# Fuel_Sensor.net
KiCad netlist of a schematic drawn in EAGLE
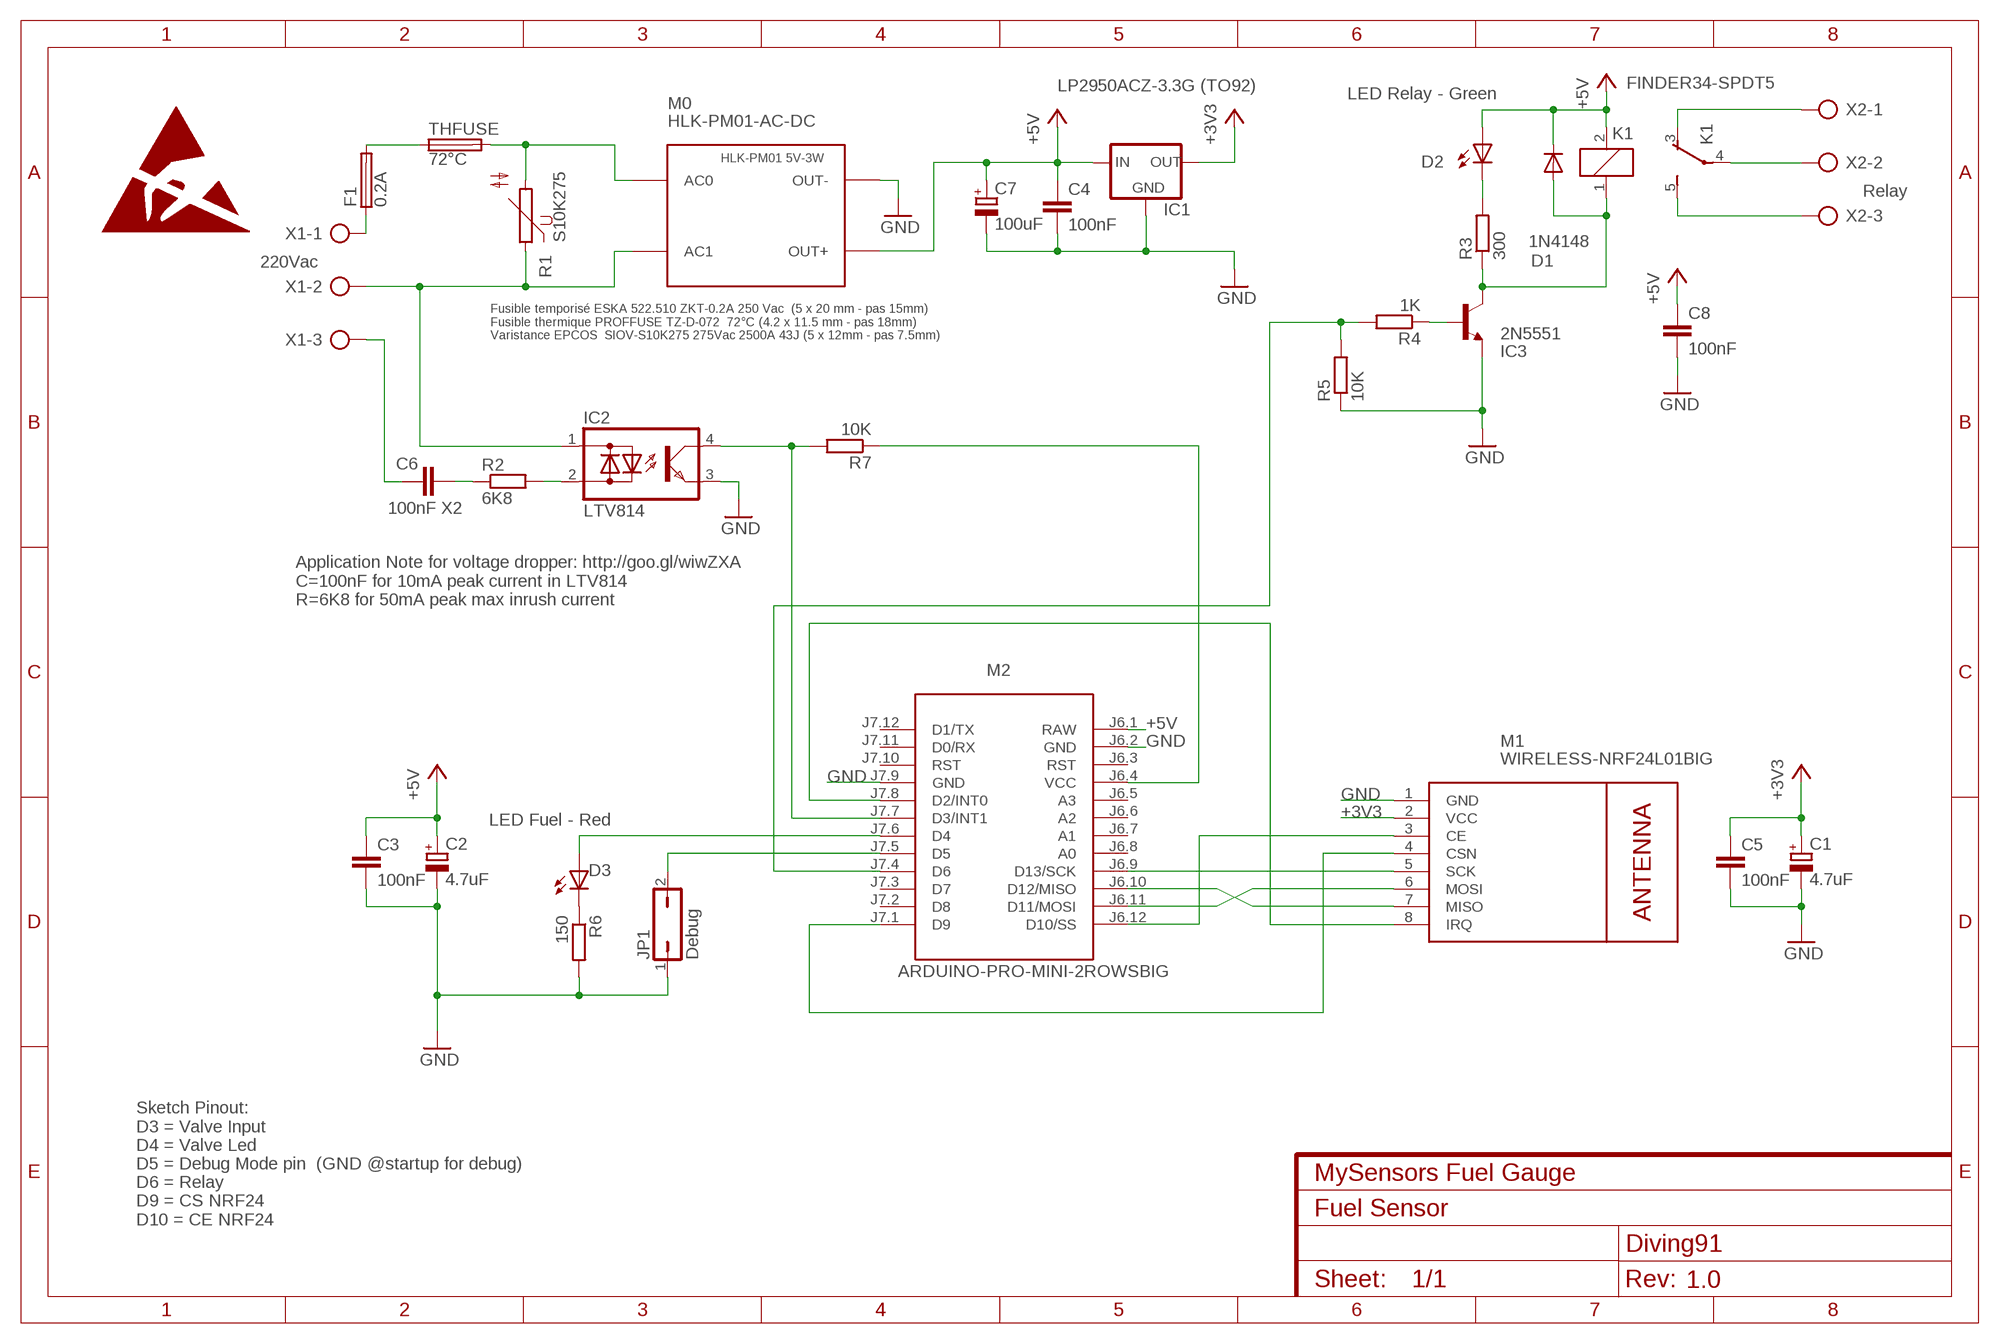
[diagram p0: schematic, sheet 1]

(export (version "E")
  (design (tool "Eeschema 10.0.6"))
  (components
    (comp (ref "C1")
      (value "4.7uF")
      (footprint "eagle-import:E2-5")
      (libsource (lib "eagle-import") (part "CPOL-RADE2-5"))
    )
    (comp (ref "C2")
      (value "4.7uF")
      (footprint "eagle-import:E2-5")
      (libsource (lib "eagle-import") (part "CPOL-RADE2-5"))
    )
    (comp (ref "C3")
      (value "100nF")
      (footprint "eagle-import:C-C320")
      (libsource (lib "eagle-import") (part "CNP-RADC320"))
    )
    (comp (ref "C4")
      (value "100nF")
      (footprint "eagle-import:C-C320")
      (libsource (lib "eagle-import") (part "CNP-RADC320"))
    )
    (comp (ref "C5")
      (value "100nF")
      (footprint "eagle-import:C-C320")
      (libsource (lib "eagle-import") (part "CNP-RADC320"))
    )
    (comp (ref "C6")
      (value "100nF X2")
      (footprint "eagle-import:C-B32922-MKPX2")
      (libsource (lib "eagle-import") (part "CNP-RADB32922"))
    )
    (comp (ref "C7")
      (value "100uF")
      (footprint "eagle-import:E3-8")
      (libsource (lib "eagle-import") (part "CPOL-RADE3-8"))
    )
    (comp (ref "C8")
      (value "100nF")
      (footprint "eagle-import:C-C320")
      (libsource (lib "eagle-import") (part "CNP-RADC320"))
    )
    (comp (ref "D1")
      (value "1N4148")
      (footprint "eagle-import:DO35")
      (libsource (lib "eagle-import") (part "1N4148DO35"))
    )
    (comp (ref "D2")
      (value "LED Relay - Green")
      (footprint "eagle-import:LED5MM")
      (libsource (lib "eagle-import") (part "LED5MM"))
    )
    (comp (ref "D3")
      (value "LED Fuel - Red")
      (footprint "eagle-import:LED5MM")
      (libsource (lib "eagle-import") (part "LED5MM"))
    )
    (comp (ref "F1")
      (value "0.2A")
      (footprint "eagle-import:PTF75")
      (libsource (lib "eagle-import") (part "PTF75"))
    )
    (comp (ref "IC1")
      (value "LP2950ACZ-3.3G (TO92)")
      (footprint "eagle-import:DC-DC-TO92L")
      (libsource (lib "eagle-import") (part "78LXXTO92L"))
    )
    (comp (ref "IC2")
      (value "LTV814")
      (footprint "eagle-import:DIL04")
      (libsource (lib "eagle-import") (part "LTV814"))
    )
    (comp (ref "IC3")
      (value "2N5551")
      (footprint "eagle-import:T-T092L")
      (libsource (lib "eagle-import") (part "T-NPNT092L"))
    )
    (comp (ref "JP1")
      (value "Debug")
      (footprint "eagle-import:JUMPER2")
      (libsource (lib "eagle-import") (part "JUMPER2"))
    )
    (comp (ref "K1")
      (value "FINDER34-SPDT5")
      (footprint "eagle-import:FINDER34-SPDT")
      (libsource (lib "eagle-import") (part "FINDER34-SPDT5"))
    )
    (comp (ref "M0")
      (value "HLK-PM01-AC-DC")
      (footprint "eagle-import:HLK-PM01-AC-DC")
      (libsource (lib "eagle-import") (part "HLK-PM01-AC-DC"))
    )
    (comp (ref "M1")
      (value "WIRELESS-NRF24L01BIG")
      (footprint "eagle-import:WIRELESS-NRF24L01-DIY")
      (libsource (lib "eagle-import") (part "WIRELESS-NRF24L01BIG"))
    )
    (comp (ref "M2")
      (value "ARDUINO-PRO-MINI-2ROWSBIG")
      (footprint "eagle-import:ARDUINO-PRO-MINI-2ROWS-DIY")
      (libsource (lib "eagle-import") (part "ARDUINO-PRO-MINI-2ROWSBIG"))
    )
    (comp (ref "R1")
      (value "S10K275")
      (footprint "eagle-import:S10K275")
      (libsource (lib "eagle-import") (part "S10K275"))
    )
    (comp (ref "R2")
      (value "6K8")
      (footprint "eagle-import:PMR02S")
      (libsource (lib "eagle-import") (part "RPMR02S"))
    )
    (comp (ref "R3")
      (value "300")
      (footprint "eagle-import:PMR0.25W")
      (libsource (lib "eagle-import") (part "RPMR0.25W"))
    )
    (comp (ref "R4")
      (value "1K")
      (footprint "eagle-import:PMR0.25W")
      (libsource (lib "eagle-import") (part "RPMR0.25W"))
    )
    (comp (ref "R5")
      (value "10K")
      (footprint "eagle-import:PMR0.25W")
      (libsource (lib "eagle-import") (part "RPMR0.25W"))
    )
    (comp (ref "R6")
      (value "150")
      (footprint "eagle-import:PMR0.25W")
      (libsource (lib "eagle-import") (part "RPMR0.25W"))
    )
    (comp (ref "R7")
      (value "10K")
      (footprint "eagle-import:PMR0.25W")
      (libsource (lib "eagle-import") (part "RPMR0.25W"))
    )
    (comp (ref "THFUSE")
      (value "72°C")
      (footprint "eagle-import:PROFFUSE-TZ-D")
      (libsource (lib "eagle-import") (part "PROFFUSE-TZ-D"))
    )
    (comp (ref "X1")
      (value "220Vac")
      (footprint "eagle-import:DG301-5.0-3")
      (libsource (lib "eagle-import") (part "DG301-5.0-3"))
    )
    (comp (ref "X2")
      (value "Relay")
      (footprint "eagle-import:DG301-5.0-3")
      (libsource (lib "eagle-import") (part "DG301-5.0-3"))
    )
  )
  (nets
    (net (code "1") (name "+3V3") (class "Default")
      (node (ref "C1") (pin "+") (pinfunction "+_+") (pintype "passive"))
      (node (ref "C5") (pin "1") (pinfunction "1_1") (pintype "passive"))
      (node (ref "IC1") (pin "OUT") (pinfunction "OUT_OUT") (pintype "passive"))
      (node (ref "M1") (pin "2") (pinfunction "VCC_2") (pintype "power_in"))
    )
    (net (code "2") (name "+5V") (class "Default")
      (node (ref "C2") (pin "+") (pinfunction "+_+") (pintype "passive"))
      (node (ref "C3") (pin "1") (pinfunction "1_1") (pintype "passive"))
      (node (ref "C4") (pin "1") (pinfunction "1_1") (pintype "passive"))
      (node (ref "C7") (pin "+") (pinfunction "+_+") (pintype "passive"))
      (node (ref "C8") (pin "1") (pinfunction "1_1") (pintype "passive"))
      (node (ref "D1") (pin "C") (pinfunction "C_C") (pintype "passive"))
      (node (ref "D2") (pin "A") (pinfunction "A_A") (pintype "passive"))
      (node (ref "IC1") (pin "IN") (pinfunction "IN_IN") (pintype "input"))
      (node (ref "K1") (pin "2") (pinfunction "2_2") (pintype "passive"))
      (node (ref "M0") (pin "OUT+") (pinfunction "OUT+_OUT+") (pintype "bidirectional"))
      (node (ref "M2") (pin "J6.1") (pinfunction "RAW_J6.1") (pintype "power_in"))
    )
    (net (code "3") (name "GND") (class "Default")
      (node (ref "C1") (pin "-") (pinfunction "-_-") (pintype "passive"))
      (node (ref "C2") (pin "-") (pinfunction "-_-") (pintype "passive"))
      (node (ref "C3") (pin "2") (pinfunction "2_2") (pintype "passive"))
      (node (ref "C4") (pin "2") (pinfunction "2_2") (pintype "passive"))
      (node (ref "C5") (pin "2") (pinfunction "2_2") (pintype "passive"))
      (node (ref "C7") (pin "-") (pinfunction "-_-") (pintype "passive"))
      (node (ref "C8") (pin "2") (pinfunction "2_2") (pintype "passive"))
      (node (ref "IC1") (pin "GND") (pinfunction "GND_GND") (pintype "input"))
      (node (ref "IC2") (pin "3") (pinfunction "E_3") (pintype "passive"))
      (node (ref "IC3") (pin "E") (pinfunction "E_E") (pintype "passive"))
      (node (ref "JP1") (pin "1") (pinfunction "1_1") (pintype "passive"))
      (node (ref "M0") (pin "OUT-") (pinfunction "OUT-_OUT-") (pintype "bidirectional"))
      (node (ref "M1") (pin "1") (pinfunction "GND_1") (pintype "power_in"))
      (node (ref "M2") (pin "J6.2") (pinfunction "GND_J6.2") (pintype "power_in"))
      (node (ref "M2") (pin "J7.9") (pinfunction "GND_J7.9") (pintype "power_in"))
      (node (ref "R5") (pin "1") (pinfunction "1_1") (pintype "passive"))
      (node (ref "R6") (pin "2") (pinfunction "2_2") (pintype "passive"))
    )
    (net (code "4") (name "Net-(C6-Pad2)") (class "Default")
      (node (ref "C6") (pin "2") (pinfunction "2_2") (pintype "passive"))
      (node (ref "R2") (pin "1") (pinfunction "1_1") (pintype "passive"))
    )
    (net (code "5") (name "Net-(D1-PadA)") (class "Default")
      (node (ref "D1") (pin "A") (pinfunction "A_A") (pintype "passive"))
      (node (ref "IC3") (pin "C") (pinfunction "C_C") (pintype "passive"))
      (node (ref "K1") (pin "1") (pinfunction "1_1") (pintype "passive"))
      (node (ref "R3") (pin "1") (pinfunction "1_1") (pintype "passive"))
    )
    (net (code "6") (name "Net-(D2-C)") (class "Default")
      (node (ref "D2") (pin "K") (pinfunction "C_K") (pintype "passive"))
      (node (ref "R3") (pin "2") (pinfunction "2_2") (pintype "passive"))
    )
    (net (code "7") (name "Net-(D3-C)") (class "Default")
      (node (ref "D3") (pin "K") (pinfunction "C_K") (pintype "passive"))
      (node (ref "R6") (pin "1") (pinfunction "1_1") (pintype "passive"))
    )
    (net (code "8") (name "Net-(F1-Pad2)") (class "Default")
      (node (ref "F1") (pin "2") (pinfunction "2_2") (pintype "passive"))
      (node (ref "THFUSE") (pin "1") (pinfunction "1_1") (pintype "passive"))
    )
    (net (code "9") (name "Net-(IC2-AC1)") (class "Default")
      (node (ref "IC2") (pin "1") (pinfunction "AC1_1") (pintype "passive"))
      (node (ref "M0") (pin "AC1") (pinfunction "AC1_AC1") (pintype "bidirectional"))
      (node (ref "R1") (pin "1") (pinfunction "1_1") (pintype "passive"))
      (node (ref "X1") (pin "2") (pinfunction "KL_2") (pintype "passive"))
    )
    (net (code "10") (name "Net-(IC2-AC2)") (class "Default")
      (node (ref "IC2") (pin "2") (pinfunction "AC2_2") (pintype "passive"))
      (node (ref "R2") (pin "2") (pinfunction "2_2") (pintype "passive"))
    )
    (net (code "11") (name "Net-(IC2-C)") (class "Default")
      (node (ref "IC2") (pin "4") (pinfunction "C_4") (pintype "passive"))
      (node (ref "M2") (pin "J7.7") (pinfunction "D3/INT1_J7.7") (pintype "bidirectional"))
      (node (ref "R7") (pin "2") (pinfunction "2_2") (pintype "passive"))
    )
    (net (code "12") (name "Net-(IC3-PadB)") (class "Default")
      (node (ref "IC3") (pin "B") (pinfunction "B_B") (pintype "passive"))
      (node (ref "R4") (pin "1") (pinfunction "1_1") (pintype "passive"))
    )
    (net (code "13") (name "Net-(K1A-O)") (class "Default")
      (node (ref "K1") (pin "3") (pinfunction "O_3") (pintype "passive"))
      (node (ref "X2") (pin "1") (pinfunction "KL_1") (pintype "passive"))
    )
    (net (code "14") (name "Net-(K1A-P)") (class "Default")
      (node (ref "K1") (pin "4") (pinfunction "P_4") (pintype "passive"))
      (node (ref "X2") (pin "2") (pinfunction "KL_2") (pintype "passive"))
    )
    (net (code "15") (name "Net-(K1A-S)") (class "Default")
      (node (ref "K1") (pin "5") (pinfunction "S_5") (pintype "passive"))
      (node (ref "X2") (pin "3") (pinfunction "KL_3") (pintype "passive"))
    )
    (net (code "16") (name "Net-(M0-PadAC0)") (class "Default")
      (node (ref "M0") (pin "AC0") (pinfunction "AC0_AC0") (pintype "bidirectional"))
      (node (ref "R1") (pin "2") (pinfunction "2_2") (pintype "passive"))
      (node (ref "THFUSE") (pin "2") (pinfunction "2_2") (pintype "passive"))
    )
    (net (code "17") (name "Net-(M1-CE)") (class "Default")
      (node (ref "M1") (pin "3") (pinfunction "CE_3") (pintype "bidirectional"))
      (node (ref "M2") (pin "J6.12") (pinfunction "D10/SS_J6.12") (pintype "bidirectional"))
    )
    (net (code "18") (name "Net-(M1-CSN)") (class "Default")
      (node (ref "M1") (pin "4") (pinfunction "CSN_4") (pintype "bidirectional"))
      (node (ref "M2") (pin "J7.1") (pinfunction "D9_J7.1") (pintype "bidirectional"))
    )
    (net (code "19") (name "Net-(M1-IRQ)") (class "Default")
      (node (ref "M1") (pin "8") (pinfunction "IRQ_8") (pintype "bidirectional"))
      (node (ref "M2") (pin "J7.8") (pinfunction "D2/INT0_J7.8") (pintype "bidirectional"))
    )
    (net (code "20") (name "Net-(M1-MISO)") (class "Default")
      (node (ref "M1") (pin "7") (pinfunction "MISO_7") (pintype "bidirectional"))
      (node (ref "M2") (pin "J6.10") (pinfunction "D12/MISO_J6.10") (pintype "bidirectional"))
    )
    (net (code "21") (name "Net-(M1-MOSI)") (class "Default")
      (node (ref "M1") (pin "6") (pinfunction "MOSI_6") (pintype "bidirectional"))
      (node (ref "M2") (pin "J6.11") (pinfunction "D11/MOSI_J6.11") (pintype "bidirectional"))
    )
    (net (code "22") (name "Net-(M1-SCK)") (class "Default")
      (node (ref "M1") (pin "5") (pinfunction "SCK_5") (pintype "bidirectional"))
      (node (ref "M2") (pin "J6.9") (pinfunction "D13/SCK_J6.9") (pintype "bidirectional"))
    )
    (net (code "23") (name "Net-(M2-D4)") (class "Default")
      (node (ref "D3") (pin "A") (pinfunction "A_A") (pintype "passive"))
      (node (ref "M2") (pin "J7.6") (pinfunction "D4_J7.6") (pintype "bidirectional"))
    )
    (net (code "24") (name "Net-(M2-D5)") (class "Default")
      (node (ref "JP1") (pin "2") (pinfunction "2_2") (pintype "passive"))
      (node (ref "M2") (pin "J7.5") (pinfunction "D5_J7.5") (pintype "bidirectional"))
    )
    (net (code "25") (name "Net-(M2-D6)") (class "Default")
      (node (ref "M2") (pin "J7.4") (pinfunction "D6_J7.4") (pintype "bidirectional"))
      (node (ref "R4") (pin "2") (pinfunction "2_2") (pintype "passive"))
      (node (ref "R5") (pin "2") (pinfunction "2_2") (pintype "passive"))
    )
    (net (code "26") (name "Net-(M2-VCC)") (class "Default")
      (node (ref "M2") (pin "J6.4") (pinfunction "VCC_J6.4") (pintype "power_in"))
      (node (ref "R7") (pin "1") (pinfunction "1_1") (pintype "passive"))
    )
    (net (code "27") (name "Net-(X1A-KL)") (class "Default")
      (node (ref "F1") (pin "1") (pinfunction "1_1") (pintype "passive"))
      (node (ref "X1") (pin "1") (pinfunction "KL_1") (pintype "passive"))
    )
    (net (code "28") (name "Net-(X1C-KL)") (class "Default")
      (node (ref "C6") (pin "1") (pinfunction "1_1") (pintype "passive"))
      (node (ref "X1") (pin "3") (pinfunction "KL_3") (pintype "passive"))
    )
    (net (code "29") (name "unconnected-(M2-A0-PadJ6.8)") (class "Default")
      (node (ref "M2") (pin "J6.8") (pinfunction "A0_J6.8") (pintype "bidirectional"))
    )
    (net (code "30") (name "unconnected-(M2-A1-PadJ6.7)") (class "Default")
      (node (ref "M2") (pin "J6.7") (pinfunction "A1_J6.7") (pintype "bidirectional"))
    )
    (net (code "31") (name "unconnected-(M2-A2-PadJ6.6)") (class "Default")
      (node (ref "M2") (pin "J6.6") (pinfunction "A2_J6.6") (pintype "bidirectional"))
    )
    (net (code "32") (name "unconnected-(M2-A3-PadJ6.5)") (class "Default")
      (node (ref "M2") (pin "J6.5") (pinfunction "A3_J6.5") (pintype "bidirectional"))
    )
    (net (code "33") (name "unconnected-(M2-D0{slash}RX-PadJ7.11)") (class "Default")
      (node (ref "M2") (pin "J7.11") (pinfunction "D0/RX_J7.11") (pintype "bidirectional"))
    )
    (net (code "34") (name "unconnected-(M2-D1{slash}TX-PadJ7.12)") (class "Default")
      (node (ref "M2") (pin "J7.12") (pinfunction "D1/TX_J7.12") (pintype "bidirectional"))
    )
    (net (code "35") (name "unconnected-(M2-D7-PadJ7.3)") (class "Default")
      (node (ref "M2") (pin "J7.3") (pinfunction "D7_J7.3") (pintype "bidirectional"))
    )
    (net (code "36") (name "unconnected-(M2-D8-PadJ7.2)") (class "Default")
      (node (ref "M2") (pin "J7.2") (pinfunction "D8_J7.2") (pintype "bidirectional"))
    )
    (net (code "37") (name "unconnected-(M2-RST-PadJ6.3)") (class "Default")
      (node (ref "M2") (pin "J6.3") (pinfunction "RST_J6.3") (pintype "bidirectional"))
    )
    (net (code "38") (name "unconnected-(M2-RST-PadJ7.10)") (class "Default")
      (node (ref "M2") (pin "J7.10") (pinfunction "RST_J7.10") (pintype "bidirectional"))
    )
  )
)
